# AEMLION-R3.net
KiCad netlist of a schematic drawn in EAGLE
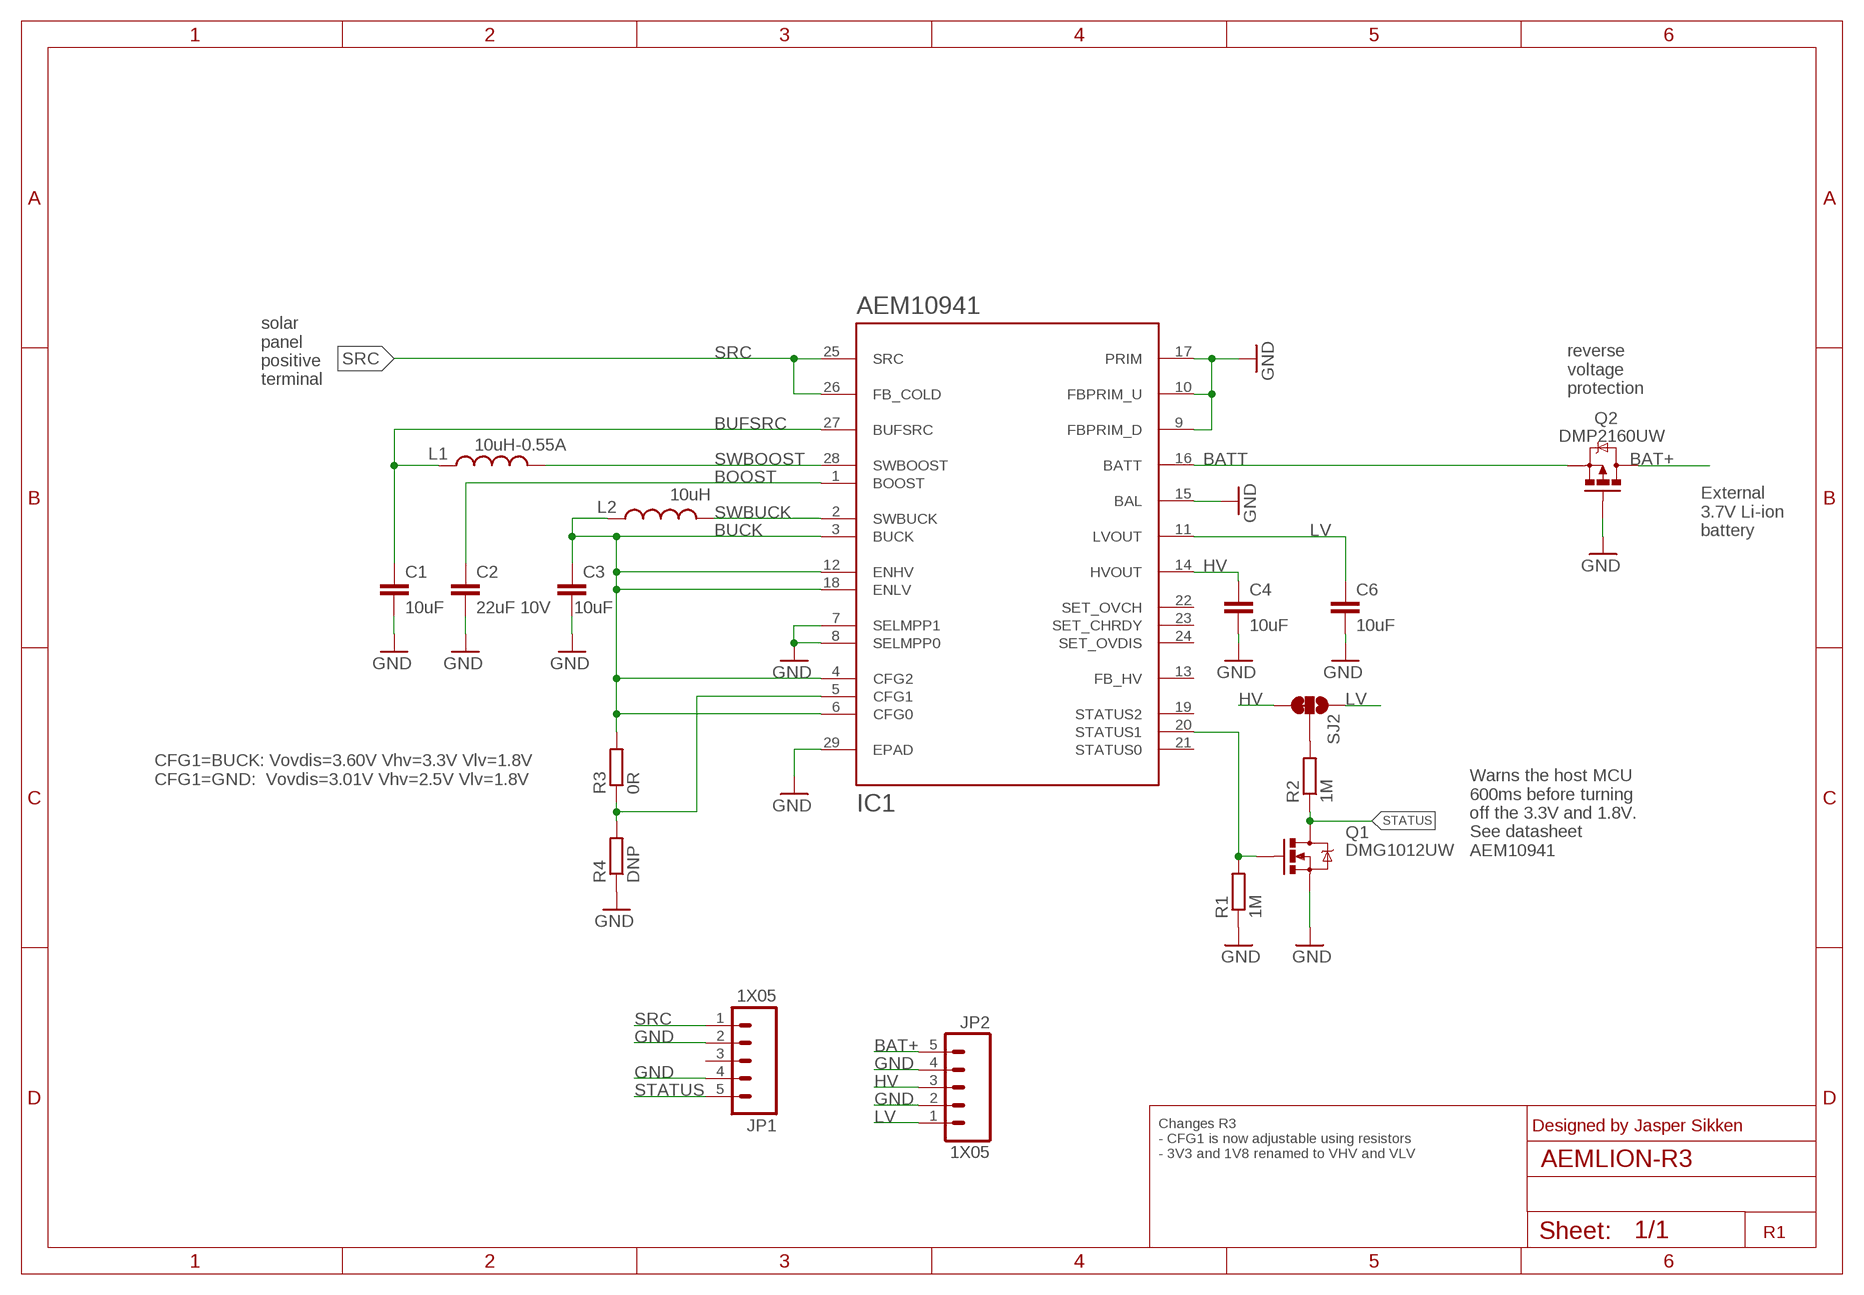
[diagram p0: schematic, sheet 1]

(export (version "E")
  (design (tool "Eeschema 10.0.6"))
  (components
    (comp (ref "C1")
      (value "10uF")
      (footprint "eagle-import:C0603")
      (fields
        (field (name "MF") "Taiyo Yuden")
        (field (name "MPN") "LMK107BBJ106MALT")
        (field (name "MF_1") "KEYSTONE")
        (field (name "MPN_1") "1049P")
      )
      (libsource (lib "eagle-import") (part "C0603_10UF"))
    )
    (comp (ref "C2")
      (value "22uF 10V")
      (footprint "eagle-import:C0603")
      (fields
        (field (name "MF") "Murata")
        (field (name "MPN") "GRM188R61A226ME15D")
        (field (name "MF_1") "TDK")
        (field (name "MPN_1") "CGA5L1X7S1A226M160AC")
      )
      (libsource (lib "eagle-import") (part "C0603_22UF"))
    )
    (comp (ref "C3")
      (value "10uF")
      (footprint "eagle-import:C0603")
      (fields
        (field (name "MF") "Taiyo Yuden")
        (field (name "MPN") "LMK107BBJ106MALT")
        (field (name "MF_1") "KEYSTONE")
        (field (name "MPN_1") "1049P")
      )
      (libsource (lib "eagle-import") (part "C0603_10UF"))
    )
    (comp (ref "C4")
      (value "10uF")
      (footprint "eagle-import:C0603")
      (fields
        (field (name "MF") "Taiyo Yuden")
        (field (name "MPN") "LMK107BBJ106MALT")
        (field (name "MF_1") "KEYSTONE")
        (field (name "MPN_1") "1049P")
      )
      (libsource (lib "eagle-import") (part "C0603_10UF"))
    )
    (comp (ref "C6")
      (value "10uF")
      (footprint "eagle-import:C0603")
      (fields
        (field (name "MF") "Taiyo Yuden")
        (field (name "MPN") "LMK107BBJ106MALT")
        (field (name "MF_1") "KEYSTONE")
        (field (name "MPN_1") "1049P")
      )
      (libsource (lib "eagle-import") (part "C0603_10UF"))
    )
    (comp (ref "IC1")
      (value "AEM10941")
      (footprint "eagle-import:QFN50P505X505X90-28")
      (fields (field (name "MF") "e-peas"))
      (libsource (lib "eagle-import") (part "AEM10941"))
    )
    (comp (ref "JP1")
      (value "1X05")
      (footprint "eagle-import:1X05_2.54MM_ROUND_NOSILK")
      (libsource (lib "eagle-import") (part "1X05"))
    )
    (comp (ref "JP2")
      (value "1X05")
      (footprint "eagle-import:1X05_2.54MM_ROUND_NOSILK")
      (libsource (lib "eagle-import") (part "1X05"))
    )
    (comp (ref "L1")
      (value "10uH-0.55A")
      (footprint "eagle-import:LPS4012")
      (fields
        (field (name "MF") "Coilcraft")
        (field (name "MPN") "LPS4012-103MRB")
        (field (name "MF_1") "BOURNS")
        (field (name "MPN_1") "SRN2009T-100M")
      )
      (libsource (lib "eagle-import") (part "L3.9X3.9_10UH_0.55A"))
    )
    (comp (ref "L2")
      (value "10uH")
      (footprint "eagle-import:L0603")
      (fields
        (field (name "MF") "TDK")
        (field (name "MPN") "MLZ1608M100WT")
        (field (name "MF_1") "TAIYO YUDEN")
        (field (name "MPN_1") "CK2125100M-T")
      )
      (libsource (lib "eagle-import") (part "L0603_10UH"))
    )
    (comp (ref "Q1")
      (value "DMG1012UW")
      (footprint "eagle-import:SOT323")
      (fields (field (name "MF") "Diodes") (field (name "MPN") "DMG1012UW-7"))
      (libsource (lib "eagle-import") (part "MOSFET-N-CHANNEL_DMG1012UW"))
    )
    (comp (ref "Q2")
      (value "DMP2160UW")
      (footprint "eagle-import:SOT323")
      (libsource (lib "eagle-import") (part "MOSFET-P-CHANNEL-DMP2160UW"))
    )
    (comp (ref "R1")
      (value "1M")
      (footprint "eagle-import:R0402")
      (fields (field (name "MF") "Walsin") (field (name "MPN") "WR04X1004FTL"))
      (libsource (lib "eagle-import") (part "R0402_1M"))
    )
    (comp (ref "R2")
      (value "1M")
      (footprint "eagle-import:R0402")
      (fields (field (name "MF") "Walsin") (field (name "MPN") "WR04X1004FTL"))
      (libsource (lib "eagle-import") (part "R0402_1M"))
    )
    (comp (ref "R3")
      (value "0R")
      (footprint "eagle-import:R0402")
      (fields (field (name "MF") "Walsin") (field (name "MPN") "WR04X1004FTL"))
      (libsource (lib "eagle-import") (part "R0402_1M"))
    )
    (comp (ref "R4")
      (value "DNP")
      (footprint "eagle-import:R0402")
      (fields (field (name "MF") "Walsin") (field (name "MPN") "WR04X1004FTL"))
      (libsource (lib "eagle-import") (part "R0402_1M"))
    )
    (comp (ref "SJ2")
      (value "SOLDERJUMPER_3WAY_12SHORT3WAY")
      (footprint "eagle-import:SJ_3S_NC_0402")
      (libsource (lib "eagle-import") (part "SOLDERJUMPER_3WAY_12SHORT3WAY"))
    )
  )
  (nets
    (net (code "1") (name "/BAT+") (class "Default")
      (node (ref "JP2") (pin "5") (pinfunction "5_5") (pintype "passive"))
      (node (ref "Q2") (pin "3") (pinfunction "D_3") (pintype "passive"))
    )
    (net (code "2") (name "/BATT") (class "Default")
      (node (ref "IC1") (pin "16") (pinfunction "BATT_16") (pintype "bidirectional"))
      (node (ref "Q2") (pin "2") (pinfunction "S_2") (pintype "passive"))
    )
    (net (code "3") (name "/BOOST") (class "Default")
      (node (ref "C2") (pin "1") (pinfunction "1_1") (pintype "passive"))
      (node (ref "IC1") (pin "1") (pinfunction "BOOST_1") (pintype "bidirectional"))
    )
    (net (code "4") (name "/BUCK") (class "Default")
      (node (ref "C3") (pin "1") (pinfunction "1_1") (pintype "passive"))
      (node (ref "IC1") (pin "12") (pinfunction "ENHV_12") (pintype "bidirectional"))
      (node (ref "IC1") (pin "18") (pinfunction "ENLV_18") (pintype "bidirectional"))
      (node (ref "IC1") (pin "3") (pinfunction "BUCK_3") (pintype "bidirectional"))
      (node (ref "IC1") (pin "4") (pinfunction "CFG2_4") (pintype "bidirectional"))
      (node (ref "IC1") (pin "6") (pinfunction "CFG0_6") (pintype "bidirectional"))
      (node (ref "L2") (pin "1") (pinfunction "1_1") (pintype "passive"))
      (node (ref "R3") (pin "2") (pinfunction "2_2") (pintype "passive"))
    )
    (net (code "5") (name "/BUFSRC") (class "Default")
      (node (ref "C1") (pin "1") (pinfunction "1_1") (pintype "passive"))
      (node (ref "IC1") (pin "27") (pinfunction "BUFSRC_27") (pintype "power_in"))
      (node (ref "L1") (pin "1") (pinfunction "1_1") (pintype "passive"))
    )
    (net (code "6") (name "/HV") (class "Default")
      (node (ref "C4") (pin "1") (pinfunction "1_1") (pintype "passive"))
      (node (ref "IC1") (pin "14") (pinfunction "HVOUT_14") (pintype "bidirectional"))
      (node (ref "JP2") (pin "3") (pinfunction "3_3") (pintype "passive"))
      (node (ref "SJ2") (pin "1") (pinfunction "1_1") (pintype "passive"))
    )
    (net (code "7") (name "/LV") (class "Default")
      (node (ref "C6") (pin "1") (pinfunction "1_1") (pintype "passive"))
      (node (ref "IC1") (pin "11") (pinfunction "LVOUT_11") (pintype "bidirectional"))
      (node (ref "JP2") (pin "1") (pinfunction "1_1") (pintype "passive"))
      (node (ref "SJ2") (pin "3") (pinfunction "3_3") (pintype "passive"))
    )
    (net (code "8") (name "/SWBOOST") (class "Default")
      (node (ref "IC1") (pin "28") (pinfunction "SWBOOST_28") (pintype "power_in"))
      (node (ref "L1") (pin "2") (pinfunction "2_2") (pintype "passive"))
    )
    (net (code "9") (name "/SWBUCK") (class "Default")
      (node (ref "IC1") (pin "2") (pinfunction "SWBUCK_2") (pintype "bidirectional"))
      (node (ref "L2") (pin "2") (pinfunction "2_2") (pintype "passive"))
    )
    (net (code "10") (name "GND") (class "Default")
      (node (ref "C1") (pin "2") (pinfunction "2_2") (pintype "passive"))
      (node (ref "C2") (pin "2") (pinfunction "2_2") (pintype "passive"))
      (node (ref "C3") (pin "2") (pinfunction "2_2") (pintype "passive"))
      (node (ref "C4") (pin "2") (pinfunction "2_2") (pintype "passive"))
      (node (ref "C6") (pin "2") (pinfunction "2_2") (pintype "passive"))
      (node (ref "IC1") (pin "10") (pinfunction "FBPRIM_U_10") (pintype "bidirectional"))
      (node (ref "IC1") (pin "15") (pinfunction "BAL_15") (pintype "bidirectional"))
      (node (ref "IC1") (pin "17") (pinfunction "PRIM_17") (pintype "bidirectional"))
      (node (ref "IC1") (pin "29") (pinfunction "EPAD_29") (pintype "power_in"))
      (node (ref "IC1") (pin "7") (pinfunction "SELMPP1_7") (pintype "bidirectional"))
      (node (ref "IC1") (pin "8") (pinfunction "SELMPP0_8") (pintype "bidirectional"))
      (node (ref "IC1") (pin "9") (pinfunction "FBPRIM_D_9") (pintype "bidirectional"))
      (node (ref "JP1") (pin "2") (pinfunction "2_2") (pintype "passive"))
      (node (ref "JP1") (pin "4") (pinfunction "4_4") (pintype "passive"))
      (node (ref "JP2") (pin "2") (pinfunction "2_2") (pintype "passive"))
      (node (ref "JP2") (pin "4") (pinfunction "4_4") (pintype "passive"))
      (node (ref "Q1") (pin "2") (pinfunction "S_2") (pintype "passive"))
      (node (ref "Q2") (pin "1") (pinfunction "G_1") (pintype "passive"))
      (node (ref "R1") (pin "1") (pinfunction "1_1") (pintype "passive"))
      (node (ref "R4") (pin "1") (pinfunction "1_1") (pintype "passive"))
    )
    (net (code "11") (name "Net-(IC1-CFG1)") (class "Default")
      (node (ref "IC1") (pin "5") (pinfunction "CFG1_5") (pintype "bidirectional"))
      (node (ref "R3") (pin "1") (pinfunction "1_1") (pintype "passive"))
      (node (ref "R4") (pin "2") (pinfunction "2_2") (pintype "passive"))
    )
    (net (code "12") (name "Net-(IC1-STATUS1)") (class "Default")
      (node (ref "IC1") (pin "20") (pinfunction "STATUS1_20") (pintype "bidirectional"))
      (node (ref "Q1") (pin "1") (pinfunction "G_1") (pintype "passive"))
      (node (ref "R1") (pin "2") (pinfunction "2_2") (pintype "passive"))
    )
    (net (code "13") (name "Net-(R2-Pad2)") (class "Default")
      (node (ref "R2") (pin "2") (pinfunction "2_2") (pintype "passive"))
      (node (ref "SJ2") (pin "2") (pinfunction "2_2") (pintype "passive"))
    )
    (net (code "14") (name "SRC") (class "Default")
      (node (ref "IC1") (pin "25") (pinfunction "SRC_25") (pintype "power_in"))
      (node (ref "IC1") (pin "26") (pinfunction "FB_COLD_26") (pintype "input"))
      (node (ref "JP1") (pin "1") (pinfunction "1_1") (pintype "passive"))
    )
    (net (code "15") (name "STATUS") (class "Default")
      (node (ref "JP1") (pin "5") (pinfunction "5_5") (pintype "passive"))
      (node (ref "Q1") (pin "3") (pinfunction "D_3") (pintype "passive"))
      (node (ref "R2") (pin "1") (pinfunction "1_1") (pintype "passive"))
    )
    (net (code "16") (name "unconnected-(IC1-FB_HV-Pad13)") (class "Default")
      (node (ref "IC1") (pin "13") (pinfunction "FB_HV_13") (pintype "bidirectional"))
    )
    (net (code "17") (name "unconnected-(IC1-SET_CHRDY-Pad23)") (class "Default")
      (node (ref "IC1") (pin "23") (pinfunction "SET_CHRDY_23") (pintype "bidirectional"))
    )
    (net (code "18") (name "unconnected-(IC1-SET_OVCH-Pad22)") (class "Default")
      (node (ref "IC1") (pin "22") (pinfunction "SET_OVCH_22") (pintype "bidirectional"))
    )
    (net (code "19") (name "unconnected-(IC1-SET_OVDIS-Pad24)") (class "Default")
      (node (ref "IC1") (pin "24") (pinfunction "SET_OVDIS_24") (pintype "bidirectional"))
    )
    (net (code "20") (name "unconnected-(IC1-STATUS0-Pad21)") (class "Default")
      (node (ref "IC1") (pin "21") (pinfunction "STATUS0_21") (pintype "bidirectional"))
    )
    (net (code "21") (name "unconnected-(IC1-STATUS2-Pad19)") (class "Default")
      (node (ref "IC1") (pin "19") (pinfunction "STATUS2_19") (pintype "bidirectional"))
    )
    (net (code "22") (name "unconnected-(JP1-Pad3)") (class "Default")
      (node (ref "JP1") (pin "3") (pinfunction "3_3") (pintype "passive"))
    )
  )
)
